# mbmc_single_board.net
KiCad netlist of a schematic drawn in EAGLE
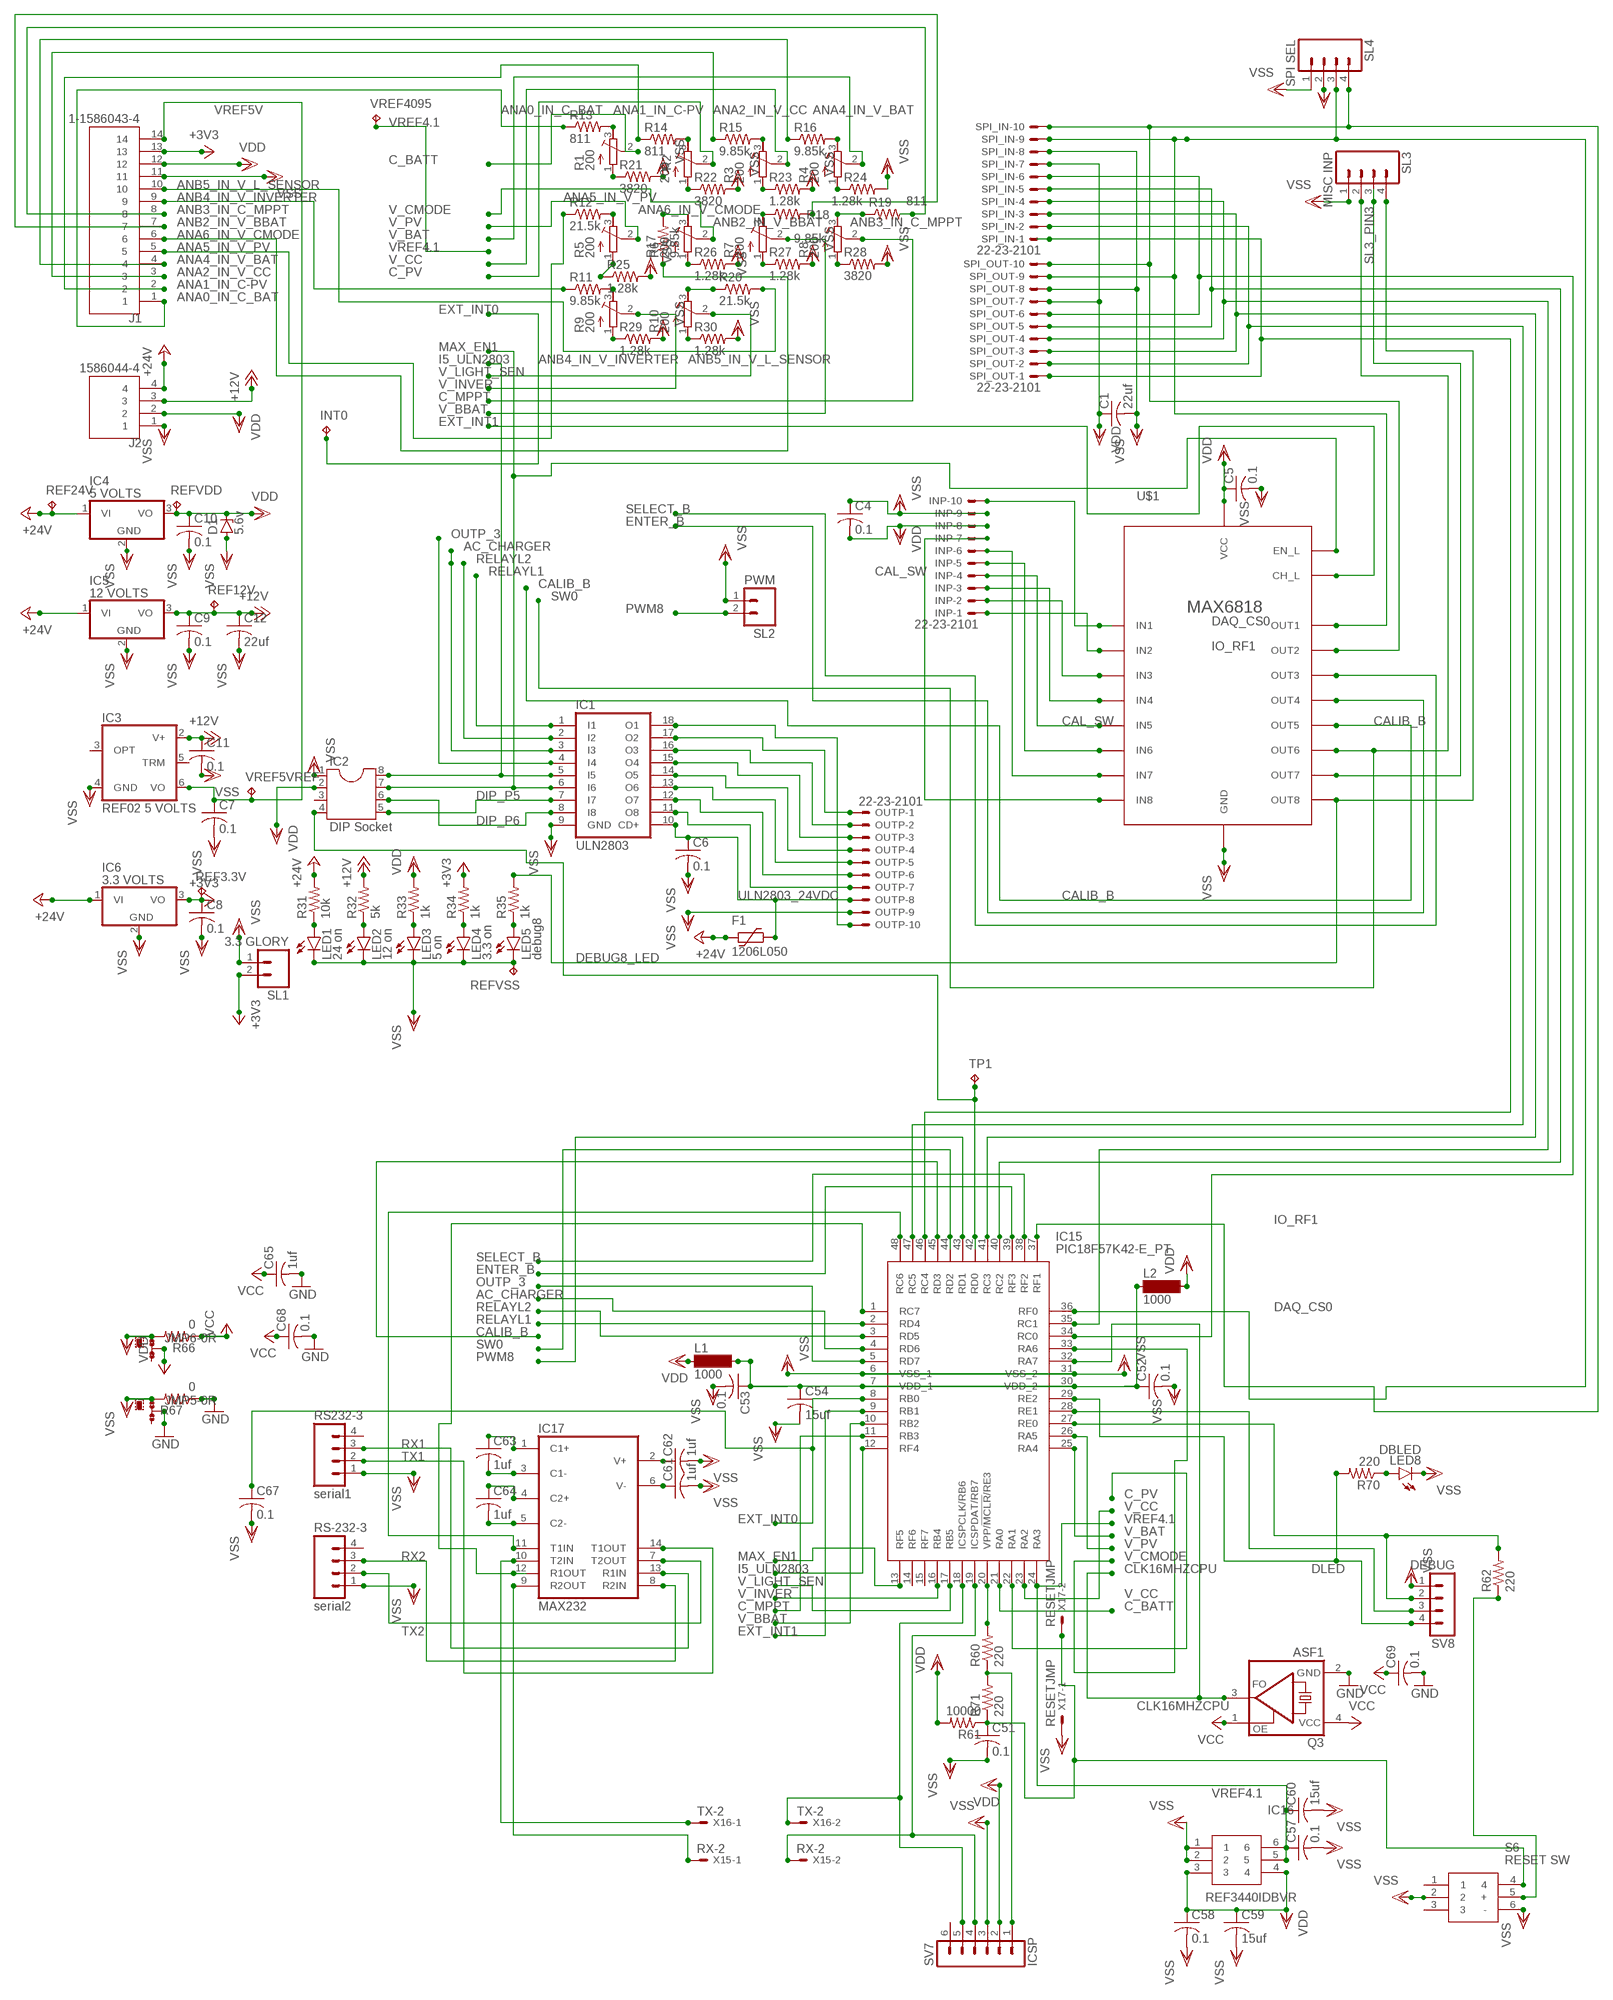
[diagram p0: schematic, sheet 1]

(export (version "E")
  (design (tool "Eeschema 10.0.6"))
  (components
    (comp (ref "C1")
      (value "22uf")
      (footprint "eagle-import:C0805")
      (libsource (lib "eagle-import") (part "C-USC0805"))
    )
    (comp (ref "C4")
      (value "0.1")
      (footprint "eagle-import:C0805")
      (libsource (lib "eagle-import") (part "C-USC0805"))
    )
    (comp (ref "C5")
      (value "0.1")
      (footprint "eagle-import:C0805")
      (libsource (lib "eagle-import") (part "C-USC0805"))
    )
    (comp (ref "C6")
      (value "0.1")
      (footprint "eagle-import:C0805")
      (libsource (lib "eagle-import") (part "C-USC0805"))
    )
    (comp (ref "C7")
      (value "0.1")
      (footprint "eagle-import:C0805")
      (libsource (lib "eagle-import") (part "C-USC0805"))
    )
    (comp (ref "C8")
      (value "0.1")
      (footprint "eagle-import:C0805")
      (libsource (lib "eagle-import") (part "C-USC0805"))
    )
    (comp (ref "C9")
      (value "0.1")
      (footprint "eagle-import:C0805")
      (libsource (lib "eagle-import") (part "C-USC0805"))
    )
    (comp (ref "C10")
      (value "0.1")
      (footprint "eagle-import:C0805")
      (libsource (lib "eagle-import") (part "C-USC0805"))
    )
    (comp (ref "C11")
      (value "0.1")
      (footprint "eagle-import:C0805")
      (libsource (lib "eagle-import") (part "C-USC0805"))
    )
    (comp (ref "C12")
      (value "22uf")
      (footprint "eagle-import:C0805")
      (libsource (lib "eagle-import") (part "C-USC0805"))
    )
    (comp (ref "C51")
      (value "0.1")
      (footprint "eagle-import:C1206")
      (libsource (lib "eagle-import") (part "C-USC1206"))
    )
    (comp (ref "C52")
      (value "0.1")
      (footprint "eagle-import:C1206")
      (libsource (lib "eagle-import") (part "C-USC1206"))
    )
    (comp (ref "C53")
      (value "0.1")
      (footprint "eagle-import:C1206")
      (libsource (lib "eagle-import") (part "C-USC1206"))
    )
    (comp (ref "C54")
      (value "15uf")
      (footprint "eagle-import:C1206")
      (libsource (lib "eagle-import") (part "C-USC1206"))
    )
    (comp (ref "C57")
      (value "0.1")
      (footprint "eagle-import:C1206")
      (libsource (lib "eagle-import") (part "C-USC1206"))
    )
    (comp (ref "C58")
      (value "0.1")
      (footprint "eagle-import:C1206")
      (libsource (lib "eagle-import") (part "C-USC1206"))
    )
    (comp (ref "C59")
      (value "15uf")
      (footprint "eagle-import:C1206")
      (libsource (lib "eagle-import") (part "C-USC1206"))
    )
    (comp (ref "C60")
      (value "15uf")
      (footprint "eagle-import:C1206")
      (libsource (lib "eagle-import") (part "C-USC1206"))
    )
    (comp (ref "C61")
      (value "1uf")
      (footprint "eagle-import:C0805")
      (libsource (lib "eagle-import") (part "C-USC0805"))
    )
    (comp (ref "C62")
      (value "1uf")
      (footprint "eagle-import:C0805")
      (libsource (lib "eagle-import") (part "C-USC0805"))
    )
    (comp (ref "C63")
      (value "1uf")
      (footprint "eagle-import:C0805")
      (libsource (lib "eagle-import") (part "C-USC0805"))
    )
    (comp (ref "C64")
      (value "1uf")
      (footprint "eagle-import:C0805")
      (libsource (lib "eagle-import") (part "C-USC0805"))
    )
    (comp (ref "C65")
      (value "1uf")
      (footprint "eagle-import:C0805")
      (libsource (lib "eagle-import") (part "C-USC0805"))
    )
    (comp (ref "C67")
      (value "0.1")
      (footprint "eagle-import:C1206")
      (libsource (lib "eagle-import") (part "C-USC1206"))
    )
    (comp (ref "C68")
      (value "0.1")
      (footprint "eagle-import:C1206")
      (libsource (lib "eagle-import") (part "C-USC1206"))
    )
    (comp (ref "C69")
      (value "0.1")
      (footprint "eagle-import:C1206")
      (libsource (lib "eagle-import") (part "C-USC1206"))
    )
    (comp (ref "D1")
      (value "5.6v")
      (footprint "eagle-import:ZDIO-2.5")
      (libsource (lib "eagle-import") (part "ZENER-DIODEZD-2.5"))
    )
    (comp (ref "F1")
      (value "1206L050")
      (footprint "eagle-import:1206L")
      (fields (field (name "MF") "Littelfuse"))
      (libsource (lib "eagle-import") (part "?1206L050"))
    )
    (comp (ref "IC1")
      (value "ULN2803")
      (footprint "eagle-import:DIL18")
      (libsource (lib "eagle-import") (part "ULN2803A"))
    )
    (comp (ref "IC2")
      (value "DIP Socket")
      (footprint "eagle-import:SOCKET-08")
      (libsource (lib "eagle-import") (part "DIL8S"))
    )
    (comp (ref "IC3")
      (value "REF02 5 VOLTS")
      (footprint "eagle-import:DIL08")
      (libsource (lib "eagle-import") (part "REF02Z"))
    )
    (comp (ref "IC4")
      (value "5 VOLTS")
      (footprint "eagle-import:TO220V")
      (libsource (lib "eagle-import") (part "78TV05"))
    )
    (comp (ref "IC5")
      (value "12 VOLTS")
      (footprint "eagle-import:TO220V")
      (libsource (lib "eagle-import") (part "78TV05"))
    )
    (comp (ref "IC6")
      (value "3.3 VOLTS")
      (footprint "eagle-import:TO220V")
      (libsource (lib "eagle-import") (part "78TV05"))
    )
    (comp (ref "IC15")
      (value "PIC18F57K42-E_PT")
      (footprint "eagle-import:QFP50P900X900X120-48N")
      (fields
        (field (name "MANUFACTURER_PART_NUMBER") "PIC18F57K42-E/PT")
        (field (name "MOUSER_PART_NUMBER") "579-PIC18F57K42-E/PT")
      )
      (libsource (lib "eagle-import") (part "PIC18F57K42-E_PT"))
    )
    (comp (ref "IC16")
      (value "REF3440IDBVR")
      (footprint "eagle-import:SOP95P280X145-6N")
      (libsource (lib "eagle-import") (part "REF3440IDBVR"))
    )
    (comp (ref "IC17")
      (value "MAX232")
      (footprint "eagle-import:DIL16")
      (fields (field (name "MF") "MAXIM") (field (name "MPN") "MAX232ACPE+"))
      (libsource (lib "eagle-import") (part "MAX232"))
    )
    (comp (ref "INP")
      (value "22-23-2101")
      (footprint "eagle-import:22-23-2101")
      (fields (field (name "MF") "MOLEX"))
      (libsource (lib "eagle-import") (part "22-23-2101"))
    )
    (comp (ref "INT0")
      (value "TPB1,27")
      (footprint "eagle-import:B1,27")
      (libsource (lib "eagle-import") (part "TPB1,27"))
    )
    (comp (ref "J1")
      (value "1-1586043-4")
      (footprint "eagle-import:TE_1-1586043-4")
      (fields (field (name "MANUFACTURER") "TE"))
      (libsource (lib "eagle-import") (part "1-1586043-4"))
    )
    (comp (ref "J2")
      (value "1586044-4")
      (footprint "eagle-import:TE_1586044-4")
      (fields (field (name "MANUFACTURER") "TE"))
      (libsource (lib "eagle-import") (part "1586044-4"))
    )
    (comp (ref "JMP5")
      (value "0R-JUMPA")
      (footprint "eagle-import:A0R-JMP")
      (libsource (lib "eagle-import") (part "0R-JUMPA"))
    )
    (comp (ref "JMP6")
      (value "0R-JUMPA")
      (footprint "eagle-import:A0R-JMP")
      (libsource (lib "eagle-import") (part "0R-JUMPA"))
    )
    (comp (ref "L1")
      (value "1000")
      (footprint "eagle-import:SM-1206")
      (libsource (lib "eagle-import") (part "SM-1206"))
    )
    (comp (ref "L2")
      (value "1000")
      (footprint "eagle-import:SM-1206")
      (libsource (lib "eagle-import") (part "SM-1206"))
    )
    (comp (ref "LED1")
      (value "24 on")
      (footprint "eagle-import:CHIPLED_1206")
      (libsource (lib "eagle-import") (part "LEDCHIPLED_1206"))
    )
    (comp (ref "LED2")
      (value "12 on")
      (footprint "eagle-import:CHIPLED_1206")
      (libsource (lib "eagle-import") (part "LEDCHIPLED_1206"))
    )
    (comp (ref "LED3")
      (value "5 on")
      (footprint "eagle-import:CHIPLED_1206")
      (libsource (lib "eagle-import") (part "LEDCHIPLED_1206"))
    )
    (comp (ref "LED4")
      (value "3.3 on")
      (footprint "eagle-import:CHIPLED_1206")
      (libsource (lib "eagle-import") (part "LEDCHIPLED_1206"))
    )
    (comp (ref "LED5")
      (value "debug8")
      (footprint "eagle-import:CHIPLED_1206")
      (libsource (lib "eagle-import") (part "LEDCHIPLED_1206"))
    )
    (comp (ref "LED8")
      (value "DBLED")
      (footprint "eagle-import:CHIPLED_1206")
      (libsource (lib "eagle-import") (part "LEDCHIPLED_1206"))
    )
    (comp (ref "OUTP")
      (value "22-23-2101")
      (footprint "eagle-import:22-23-2101")
      (fields (field (name "MF") "MOLEX"))
      (libsource (lib "eagle-import") (part "22-23-2101"))
    )
    (comp (ref "Q3")
      (value "ASF1")
      (footprint "eagle-import:ASF")
      (libsource (lib "eagle-import") (part "ASF1"))
    )
    (comp (ref "R1")
      (value "200")
      (footprint "eagle-import:RTRIM3339P")
      (libsource (lib "eagle-import") (part "R-TRIMM3339P"))
    )
    (comp (ref "R2")
      (value "200")
      (footprint "eagle-import:RTRIM3339P")
      (libsource (lib "eagle-import") (part "R-TRIMM3339P"))
    )
    (comp (ref "R3")
      (value "200")
      (footprint "eagle-import:RTRIM3339P")
      (libsource (lib "eagle-import") (part "R-TRIMM3339P"))
    )
    (comp (ref "R4")
      (value "200")
      (footprint "eagle-import:RTRIM3339P")
      (libsource (lib "eagle-import") (part "R-TRIMM3339P"))
    )
    (comp (ref "R5")
      (value "200")
      (footprint "eagle-import:RTRIM3339P")
      (libsource (lib "eagle-import") (part "R-TRIMM3339P"))
    )
    (comp (ref "R6")
      (value "200")
      (footprint "eagle-import:RTRIM3339P")
      (libsource (lib "eagle-import") (part "R-TRIMM3339P"))
    )
    (comp (ref "R7")
      (value "200")
      (footprint "eagle-import:RTRIM3339P")
      (libsource (lib "eagle-import") (part "R-TRIMM3339P"))
    )
    (comp (ref "R8")
      (value "200")
      (footprint "eagle-import:RTRIM3339P")
      (libsource (lib "eagle-import") (part "R-TRIMM3339P"))
    )
    (comp (ref "R9")
      (value "200")
      (footprint "eagle-import:RTRIM3339P")
      (libsource (lib "eagle-import") (part "R-TRIMM3339P"))
    )
    (comp (ref "R10")
      (value "200")
      (footprint "eagle-import:RTRIM3339P")
      (libsource (lib "eagle-import") (part "R-TRIMM3339P"))
    )
    (comp (ref "R11")
      (value "9.85k")
      (footprint "eagle-import:R0805")
      (libsource (lib "eagle-import") (part "R-US_R0805"))
    )
    (comp (ref "R12")
      (value "21.5k")
      (footprint "eagle-import:R0805")
      (libsource (lib "eagle-import") (part "R-US_R0805"))
    )
    (comp (ref "R13")
      (value "811")
      (footprint "eagle-import:R0805")
      (libsource (lib "eagle-import") (part "R-US_R0805"))
    )
    (comp (ref "R14")
      (value "811")
      (footprint "eagle-import:R0805")
      (libsource (lib "eagle-import") (part "R-US_R0805"))
    )
    (comp (ref "R15")
      (value "9.85k")
      (footprint "eagle-import:R0805")
      (libsource (lib "eagle-import") (part "R-US_R0805"))
    )
    (comp (ref "R16")
      (value "9.85k")
      (footprint "eagle-import:R0805")
      (libsource (lib "eagle-import") (part "R-US_R0805"))
    )
    (comp (ref "R17")
      (value "9.85k")
      (footprint "eagle-import:R0805")
      (libsource (lib "eagle-import") (part "R-US_R0805"))
    )
    (comp (ref "R18")
      (value "9.85k")
      (footprint "eagle-import:R0805")
      (libsource (lib "eagle-import") (part "R-US_R0805"))
    )
    (comp (ref "R19")
      (value "811")
      (footprint "eagle-import:R0805")
      (libsource (lib "eagle-import") (part "R-US_R0805"))
    )
    (comp (ref "R20")
      (value "21.5k")
      (footprint "eagle-import:R0805")
      (libsource (lib "eagle-import") (part "R-US_R0805"))
    )
    (comp (ref "R21")
      (value "3820")
      (footprint "eagle-import:R0805")
      (libsource (lib "eagle-import") (part "R-US_R0805"))
    )
    (comp (ref "R22")
      (value "3820")
      (footprint "eagle-import:R0805")
      (libsource (lib "eagle-import") (part "R-US_R0805"))
    )
    (comp (ref "R23")
      (value "1.28k")
      (footprint "eagle-import:R0805")
      (libsource (lib "eagle-import") (part "R-US_R0805"))
    )
    (comp (ref "R24")
      (value "1.28k")
      (footprint "eagle-import:R0805")
      (libsource (lib "eagle-import") (part "R-US_R0805"))
    )
    (comp (ref "R25")
      (value "1.28k")
      (footprint "eagle-import:R0805")
      (libsource (lib "eagle-import") (part "R-US_R0805"))
    )
    (comp (ref "R26")
      (value "1.28k")
      (footprint "eagle-import:R0805")
      (libsource (lib "eagle-import") (part "R-US_R0805"))
    )
    (comp (ref "R27")
      (value "1.28k")
      (footprint "eagle-import:R0805")
      (libsource (lib "eagle-import") (part "R-US_R0805"))
    )
    (comp (ref "R28")
      (value "3820")
      (footprint "eagle-import:R0805")
      (libsource (lib "eagle-import") (part "R-US_R0805"))
    )
    (comp (ref "R29")
      (value "1.28k")
      (footprint "eagle-import:R0805")
      (libsource (lib "eagle-import") (part "R-US_R0805"))
    )
    (comp (ref "R30")
      (value "1.28k")
      (footprint "eagle-import:R0805")
      (libsource (lib "eagle-import") (part "R-US_R0805"))
    )
    (comp (ref "R31")
      (value "10k")
      (footprint "eagle-import:R0805")
      (libsource (lib "eagle-import") (part "R-US_R0805"))
    )
    (comp (ref "R32")
      (value "5k")
      (footprint "eagle-import:R0805")
      (libsource (lib "eagle-import") (part "R-US_R0805"))
    )
    (comp (ref "R33")
      (value "1k")
      (footprint "eagle-import:R0805")
      (libsource (lib "eagle-import") (part "R-US_R0805"))
    )
    (comp (ref "R34")
      (value "1k")
      (footprint "eagle-import:R0805")
      (libsource (lib "eagle-import") (part "R-US_R0805"))
    )
    (comp (ref "R35")
      (value "1k")
      (footprint "eagle-import:R0805")
      (libsource (lib "eagle-import") (part "R-US_R0805"))
    )
    (comp (ref "R60")
      (value "220")
      (footprint "eagle-import:R1206")
      (libsource (lib "eagle-import") (part "R-US_R1206"))
    )
    (comp (ref "R61")
      (value "10000")
      (footprint "eagle-import:R1206")
      (libsource (lib "eagle-import") (part "R-US_R1206"))
    )
    (comp (ref "R62")
      (value "220")
      (footprint "eagle-import:R1206")
      (libsource (lib "eagle-import") (part "R-US_R1206"))
    )
    (comp (ref "R66")
      (value "0")
      (footprint "eagle-import:R1206")
      (libsource (lib "eagle-import") (part "R-US_R1206"))
    )
    (comp (ref "R67")
      (value "0")
      (footprint "eagle-import:R1206")
      (libsource (lib "eagle-import") (part "R-US_R1206"))
    )
    (comp (ref "R70")
      (value "220")
      (footprint "eagle-import:R1206")
      (libsource (lib "eagle-import") (part "R-US_R1206"))
    )
    (comp (ref "R71")
      (value "220")
      (footprint "eagle-import:R1206")
      (libsource (lib "eagle-import") (part "R-US_R1206"))
    )
    (comp (ref "REF3.3V")
      (value "TPB1,27")
      (footprint "eagle-import:B1,27")
      (libsource (lib "eagle-import") (part "TPB1,27"))
    )
    (comp (ref "REF12V")
      (value "TPB1,27")
      (footprint "eagle-import:B1,27")
      (libsource (lib "eagle-import") (part "TPB1,27"))
    )
    (comp (ref "REF24V")
      (value "TPB1,27")
      (footprint "eagle-import:B1,27")
      (libsource (lib "eagle-import") (part "TPB1,27"))
    )
    (comp (ref "REFVDD")
      (value "TPB1,27")
      (footprint "eagle-import:B1,27")
      (libsource (lib "eagle-import") (part "TPB1,27"))
    )
    (comp (ref "REFVSS")
      (value "TPB1,27")
      (footprint "eagle-import:B1,27")
      (libsource (lib "eagle-import") (part "TPB1,27"))
    )
    (comp (ref "RS-232-3")
      (value "serial2")
      (footprint "eagle-import:04P")
      (libsource (lib "eagle-import") (part "M04"))
    )
    (comp (ref "RS232-3")
      (value "serial1")
      (footprint "eagle-import:04P")
      (libsource (lib "eagle-import") (part "M04"))
    )
    (comp (ref "S6")
      (value "RESET SW")
      (footprint "eagle-import:B3W-9_1-LED")
      (fields
        (field (name "MANUFACTURER_PART_NUMBER") "B3W-9000-Y1N")
        (field (name "MOUSER_PART_NUMBER") "653-B3W-9000-Y1N")
        (field (name "RS_PART_NUMBER") "0492777P")
      )
      (libsource (lib "eagle-import") (part "B3W-9000-Y1N"))
    )
    (comp (ref "SL1")
      (value "3.3 GLORY")
      (footprint "eagle-import:02P")
      (libsource (lib "eagle-import") (part "M02"))
    )
    (comp (ref "SL2")
      (value "PWM")
      (footprint "eagle-import:02P")
      (libsource (lib "eagle-import") (part "M02"))
    )
    (comp (ref "SL3")
      (value "MISC INP")
      (footprint "eagle-import:04P")
      (libsource (lib "eagle-import") (part "M04"))
    )
    (comp (ref "SL4")
      (value "SPI SEL")
      (footprint "eagle-import:04P")
      (libsource (lib "eagle-import") (part "M04"))
    )
    (comp (ref "SPI_IN")
      (value "22-23-2101")
      (footprint "eagle-import:22-23-2101")
      (fields (field (name "MF") "MOLEX"))
      (libsource (lib "eagle-import") (part "22-23-2101"))
    )
    (comp (ref "SPI_OUT")
      (value "22-23-2101")
      (footprint "eagle-import:22-23-2101")
      (fields (field (name "MF") "MOLEX"))
      (libsource (lib "eagle-import") (part "22-23-2101"))
    )
    (comp (ref "SV7")
      (value "ICSP")
      (footprint "eagle-import:MA06-1")
      (libsource (lib "eagle-import") (part "MA06-1"))
    )
    (comp (ref "SV8")
      (value "DEBUG")
      (footprint "eagle-import:MA04-1")
      (libsource (lib "eagle-import") (part "MA04-1"))
    )
    (comp (ref "TP1")
      (value "TPB1,27")
      (footprint "eagle-import:B1,27")
      (libsource (lib "eagle-import") (part "TPB1,27"))
    )
    (comp (ref "U$1")
      (value "MAX6818")
      (footprint "eagle-import:SSOP20")
      (fields (field (name "MF") "Maxim Integrated"))
      (libsource (lib "eagle-import") (part "MAX6818"))
    )
    (comp (ref "VREF5VREF")
      (value "TPB1,27")
      (footprint "eagle-import:B1,27")
      (libsource (lib "eagle-import") (part "TPB1,27"))
    )
    (comp (ref "VREF4095")
      (value "TPB1,27")
      (footprint "eagle-import:B1,27")
      (libsource (lib "eagle-import") (part "TPB1,27"))
    )
    (comp (ref "X15")
      (value "RX-2")
      (footprint "eagle-import:332-02")
      (libsource (lib "eagle-import") (part "332-02"))
    )
    (comp (ref "X16")
      (value "TX-2")
      (footprint "eagle-import:332-02")
      (libsource (lib "eagle-import") (part "332-02"))
    )
    (comp (ref "X17")
      (value "RESETJMP")
      (footprint "eagle-import:332-02")
      (libsource (lib "eagle-import") (part "332-02"))
    )
  )
  (nets
    (net (code "1") (name "+3V3") (class "Default")
      (node (ref "C8") (pin "1") (pinfunction "1_1") (pintype "passive"))
      (node (ref "IC6") (pin "3") (pinfunction "VO_3") (pintype "passive"))
      (node (ref "J1") (pin "13") (pinfunction "13_13") (pintype "passive"))
      (node (ref "R34") (pin "2") (pinfunction "2_2") (pintype "passive"))
      (node (ref "REF3.3V") (pin "TP") (pinfunction "TP_TP") (pintype "input"))
      (node (ref "SL1") (pin "2") (pinfunction "2_2") (pintype "passive"))
    )
    (net (code "2") (name "+12V") (class "Default")
      (node (ref "C11") (pin "1") (pinfunction "1_1") (pintype "passive"))
      (node (ref "C12") (pin "1") (pinfunction "1_1") (pintype "passive"))
      (node (ref "C9") (pin "1") (pinfunction "1_1") (pintype "passive"))
      (node (ref "IC3") (pin "2") (pinfunction "V+_2") (pintype "power_in"))
      (node (ref "IC5") (pin "3") (pinfunction "VO_3") (pintype "passive"))
      (node (ref "J2") (pin "3") (pinfunction "3_3") (pintype "passive"))
      (node (ref "R32") (pin "2") (pinfunction "2_2") (pintype "passive"))
      (node (ref "REF12V") (pin "TP") (pinfunction "TP_TP") (pintype "input"))
    )
    (net (code "3") (name "+24V") (class "Default")
      (node (ref "F1") (pin "2") (pinfunction "2_2") (pintype "passive"))
      (node (ref "IC4") (pin "1") (pinfunction "VI_1") (pintype "input"))
      (node (ref "IC5") (pin "1") (pinfunction "VI_1") (pintype "input"))
      (node (ref "IC6") (pin "1") (pinfunction "VI_1") (pintype "input"))
      (node (ref "J2") (pin "4") (pinfunction "4_4") (pintype "passive"))
      (node (ref "R31") (pin "2") (pinfunction "2_2") (pintype "passive"))
      (node (ref "REF24V") (pin "TP") (pinfunction "TP_TP") (pintype "input"))
    )
    (net (code "4") (name "/AC_CHARGER") (class "Default")
      (node (ref "IC1") (pin "3") (pinfunction "I3_3") (pintype "input"))
      (node (ref "IC15") (pin "4") (pinfunction "RD6_4") (pintype "bidirectional"))
    )
    (net (code "5") (name "/ANA0_IN_C_BAT") (class "Default")
      (node (ref "J1") (pin "1") (pinfunction "1_1") (pintype "passive"))
      (node (ref "R13") (pin "1") (pinfunction "1_1") (pintype "passive"))
    )
    (net (code "6") (name "/ANA1_IN_C-PV") (class "Default")
      (node (ref "J1") (pin "2") (pinfunction "2_2") (pintype "passive"))
      (node (ref "R14") (pin "1") (pinfunction "1_1") (pintype "passive"))
    )
    (net (code "7") (name "/ANA2_IN_V_CC") (class "Default")
      (node (ref "J1") (pin "3") (pinfunction "3_3") (pintype "passive"))
      (node (ref "R15") (pin "1") (pinfunction "1_1") (pintype "passive"))
    )
    (net (code "8") (name "/ANA4_IN_V_BAT") (class "Default")
      (node (ref "J1") (pin "4") (pinfunction "4_4") (pintype "passive"))
      (node (ref "R16") (pin "1") (pinfunction "1_1") (pintype "passive"))
    )
    (net (code "9") (name "/ANA5_IN_V_PV") (class "Default")
      (node (ref "J1") (pin "5") (pinfunction "5_5") (pintype "passive"))
      (node (ref "R12") (pin "1") (pinfunction "1_1") (pintype "passive"))
    )
    (net (code "10") (name "/ANA6_IN_V_CMODE") (class "Default")
      (node (ref "J1") (pin "6") (pinfunction "6_6") (pintype "passive"))
      (node (ref "R17") (pin "1") (pinfunction "1_1") (pintype "passive"))
    )
    (net (code "11") (name "/ANB2_IN_V_BBAT") (class "Default")
      (node (ref "J1") (pin "7") (pinfunction "7_7") (pintype "passive"))
      (node (ref "R18") (pin "2") (pinfunction "2_2") (pintype "passive"))
    )
    (net (code "12") (name "/ANB3_IN_C_MPPT") (class "Default")
      (node (ref "J1") (pin "8") (pinfunction "8_8") (pintype "passive"))
      (node (ref "R19") (pin "2") (pinfunction "2_2") (pintype "passive"))
    )
    (net (code "13") (name "/ANB4_IN_V_INVERTER") (class "Default")
      (node (ref "J1") (pin "9") (pinfunction "9_9") (pintype "passive"))
      (node (ref "R11") (pin "1") (pinfunction "1_1") (pintype "passive"))
    )
    (net (code "14") (name "/ANB5_IN_V_L_SENSOR") (class "Default")
      (node (ref "J1") (pin "10") (pinfunction "10_10") (pintype "passive"))
      (node (ref "R20") (pin "2") (pinfunction "2_2") (pintype "passive"))
    )
    (net (code "15") (name "/CALIB_B") (class "Default")
      (node (ref "IC15") (pin "45") (pinfunction "RD3_45") (pintype "bidirectional"))
      (node (ref "U$1") (pin "OUT5") (pinfunction "OUT5_OUT5") (pintype "bidirectional"))
    )
    (net (code "16") (name "/CAL_SW") (class "Default")
      (node (ref "INP") (pin "4") (pinfunction "S_4") (pintype "passive"))
      (node (ref "U$1") (pin "IN5") (pinfunction "IN5_IN5") (pintype "bidirectional"))
    )
    (net (code "17") (name "/CLK16MHZCPU") (class "Default")
      (node (ref "IC15") (pin "32") (pinfunction "RA7_32") (pintype "bidirectional"))
      (node (ref "Q3") (pin "3") (pinfunction "FO_3") (pintype "output"))
    )
    (net (code "18") (name "/C_BATT") (class "Default")
      (node (ref "IC15") (pin "21") (pinfunction "RA0_21") (pintype "bidirectional"))
      (node (ref "R1") (pin "2") (pinfunction "S_2") (pintype "passive"))
    )
    (net (code "19") (name "/C_MPPT") (class "Default")
      (node (ref "IC15") (pin "11") (pinfunction "RB3_11") (pintype "bidirectional"))
      (node (ref "R8") (pin "2") (pinfunction "S_2") (pintype "passive"))
    )
    (net (code "20") (name "/C_PV") (class "Default")
      (node (ref "IC15") (pin "22") (pinfunction "RA1_22") (pintype "bidirectional"))
      (node (ref "R2") (pin "2") (pinfunction "S_2") (pintype "passive"))
    )
    (net (code "21") (name "/DAQ_CS0") (class "Default")
      (node (ref "IC15") (pin "36") (pinfunction "RF0_36") (pintype "bidirectional"))
      (node (ref "SL4") (pin "3") (pinfunction "3_3") (pintype "passive"))
      (node (ref "SPI_IN") (pin "9") (pinfunction "S_9") (pintype "passive"))
      (node (ref "SPI_OUT") (pin "9") (pinfunction "S_9") (pintype "passive"))
      (node (ref "U$1") (pin "OUT1") (pinfunction "OUT1_OUT1") (pintype "bidirectional"))
    )
    (net (code "22") (name "/DEBUG8_LED") (class "Default")
      (node (ref "R35") (pin "2") (pinfunction "2_2") (pintype "passive"))
      (node (ref "SL3") (pin "4") (pinfunction "4_4") (pintype "passive"))
      (node (ref "U$1") (pin "OUT8") (pinfunction "OUT8_OUT8") (pintype "bidirectional"))
    )
    (net (code "23") (name "/DIP_P5") (class "Default")
      (node (ref "IC1") (pin "7") (pinfunction "I7_7") (pintype "input"))
      (node (ref "IC2") (pin "5") (pinfunction "5_5") (pintype "passive"))
    )
    (net (code "24") (name "/DIP_P6") (class "Default")
      (node (ref "IC1") (pin "8") (pinfunction "I8_8") (pintype "input"))
      (node (ref "IC2") (pin "6") (pinfunction "6_6") (pintype "passive"))
    )
    (net (code "25") (name "/DLED") (class "Default")
      (node (ref "IC15") (pin "29") (pinfunction "RE2_29") (pintype "bidirectional"))
      (node (ref "R70") (pin "2") (pinfunction "2_2") (pintype "passive"))
      (node (ref "SV8") (pin "4") (pinfunction "4_4") (pintype "passive"))
    )
    (net (code "26") (name "/ENTER_B") (class "Default")
      (node (ref "IC15") (pin "39") (pinfunction "RF3_39") (pintype "bidirectional"))
      (node (ref "U$1") (pin "OUT4") (pinfunction "OUT4_OUT4") (pintype "bidirectional"))
    )
    (net (code "27") (name "/EXT_INT0") (class "Default")
      (node (ref "C67") (pin "1") (pinfunction "1_1") (pintype "passive"))
      (node (ref "IC15") (pin "8") (pinfunction "RB0_8") (pintype "bidirectional"))
      (node (ref "INT0") (pin "TP") (pinfunction "TP_TP") (pintype "input"))
    )
    (net (code "28") (name "/EXT_INT1") (class "Default")
      (node (ref "IC15") (pin "9") (pinfunction "RB1_9") (pintype "bidirectional"))
      (node (ref "U$1") (pin "CH_L") (pinfunction "CH_L_CH_L") (pintype "bidirectional"))
    )
    (net (code "29") (name "/I5_ULN2803") (class "Default")
      (node (ref "IC1") (pin "5") (pinfunction "I5_5") (pintype "input"))
      (node (ref "IC15") (pin "12") (pinfunction "RF4_12") (pintype "bidirectional"))
      (node (ref "IC2") (pin "8") (pinfunction "8_8") (pintype "passive"))
    )
    (net (code "30") (name "/IO_RF1") (class "Default")
      (node (ref "IC15") (pin "37") (pinfunction "RF1_37") (pintype "bidirectional"))
      (node (ref "SL4") (pin "4") (pinfunction "4_4") (pintype "passive"))
      (node (ref "SPI_IN") (pin "10") (pinfunction "S_10") (pintype "passive"))
      (node (ref "SPI_OUT") (pin "10") (pinfunction "S_10") (pintype "passive"))
      (node (ref "U$1") (pin "OUT2") (pinfunction "OUT2_OUT2") (pintype "bidirectional"))
    )
    (net (code "31") (name "/MAX_EN1") (class "Default")
      (node (ref "IC1") (pin "6") (pinfunction "I6_6") (pintype "input"))
      (node (ref "IC15") (pin "13") (pinfunction "RF5_13") (pintype "bidirectional"))
      (node (ref "IC2") (pin "7") (pinfunction "7_7") (pintype "passive"))
      (node (ref "U$1") (pin "EN_L") (pinfunction "EN_L_EN_L") (pintype "bidirectional"))
    )
    (net (code "32") (name "/OUTP_3") (class "Default")
      (node (ref "IC1") (pin "4") (pinfunction "I4_4") (pintype "input"))
      (node (ref "IC15") (pin "5") (pinfunction "RD7_5") (pintype "bidirectional"))
    )
    (net (code "33") (name "/PWM8") (class "Default")
      (node (ref "IC15") (pin "43") (pinfunction "RD1_43") (pintype "bidirectional"))
      (node (ref "SL2") (pin "2") (pinfunction "2_2") (pintype "passive"))
    )
    (net (code "34") (name "/RELAYL1") (class "Default")
      (node (ref "IC1") (pin "1") (pinfunction "I1_1") (pintype "input"))
      (node (ref "IC15") (pin "2") (pinfunction "RD4_2") (pintype "bidirectional"))
    )
    (net (code "35") (name "/RELAYL2") (class "Default")
      (node (ref "IC1") (pin "2") (pinfunction "I2_2") (pintype "input"))
      (node (ref "IC15") (pin "3") (pinfunction "RD5_3") (pintype "bidirectional"))
    )
    (net (code "36") (name "/RX1") (class "Default")
      (node (ref "IC17") (pin "13") (pinfunction "R1IN_13") (pintype "input"))
      (node (ref "RS232-3") (pin "3") (pinfunction "3_3") (pintype "passive"))
    )
    (net (code "37") (name "/RX2") (class "Default")
      (node (ref "IC17") (pin "8") (pinfunction "R2IN_8") (pintype "input"))
      (node (ref "RS-232-3") (pin "3") (pinfunction "3_3") (pintype "passive"))
    )
    (net (code "38") (name "/SELECT_B") (class "Default")
      (node (ref "IC15") (pin "38") (pinfunction "RF2_38") (pintype "bidirectional"))
      (node (ref "U$1") (pin "OUT3") (pinfunction "OUT3_OUT3") (pintype "bidirectional"))
    )
    (net (code "39") (name "/SL3_PIN3") (class "Default")
      (node (ref "SL3") (pin "3") (pinfunction "3_3") (pintype "passive"))
      (node (ref "U$1") (pin "OUT7") (pinfunction "OUT7_OUT7") (pintype "bidirectional"))
    )
    (net (code "40") (name "/SW0") (class "Default")
      (node (ref "IC15") (pin "44") (pinfunction "RD2_44") (pintype "bidirectional"))
      (node (ref "SL3") (pin "2") (pinfunction "2_2") (pintype "passive"))
      (node (ref "U$1") (pin "OUT6") (pinfunction "OUT6_OUT6") (pintype "bidirectional"))
    )
    (net (code "41") (name "/TX1") (class "Default")
      (node (ref "IC17") (pin "14") (pinfunction "T1OUT_14") (pintype "output"))
      (node (ref "RS232-3") (pin "2") (pinfunction "2_2") (pintype "passive"))
    )
    (net (code "42") (name "/TX2") (class "Default")
      (node (ref "IC17") (pin "7") (pinfunction "T2OUT_7") (pintype "output"))
      (node (ref "RS-232-3") (pin "2") (pinfunction "2_2") (pintype "passive"))
    )
    (net (code "43") (name "/ULN2803_24VDC") (class "Default")
      (node (ref "C6") (pin "1") (pinfunction "1_1") (pintype "passive"))
      (node (ref "F1") (pin "1") (pinfunction "1_1") (pintype "passive"))
      (node (ref "IC1") (pin "10") (pinfunction "CD+_10") (pintype "passive"))
      (node (ref "OUTP") (pin "8") (pinfunction "S_8") (pintype "passive"))
    )
    (net (code "44") (name "/VREF4.1") (class "Default")
      (node (ref "C57") (pin "1") (pinfunction "1_1") (pintype "passive"))
      (node (ref "C60") (pin "1") (pinfunction "1_1") (pintype "passive"))
      (node (ref "IC15") (pin "24") (pinfunction "RA3_24") (pintype "bidirectional"))
      (node (ref "IC16") (pin "5") (pinfunction "5_5") (pintype "bidirectional"))
      (node (ref "IC16") (pin "6") (pinfunction "6_6") (pintype "bidirectional"))
      (node (ref "VREF4095") (pin "TP") (pinfunction "TP_TP") (pintype "input"))
    )
    (net (code "45") (name "/VREF5V") (class "Default")
      (node (ref "C7") (pin "1") (pinfunction "1_1") (pintype "passive"))
      (node (ref "IC3") (pin "6") (pinfunction "VO_6") (pintype "output"))
      (node (ref "J1") (pin "14") (pinfunction "14_14") (pintype "passive"))
      (node (ref "VREF5VREF") (pin "TP") (pinfunction "TP_TP") (pintype "input"))
    )
    (net (code "46") (name "/V_BAT") (class "Default")
      (node (ref "IC15") (pin "25") (pinfunction "RA4_25") (pintype "bidirectional"))
      (node (ref "R4") (pin "2") (pinfunction "S_2") (pintype "passive"))
    )
    (net (code "47") (name "/V_BBAT") (class "Default")
      (node (ref "IC15") (pin "10") (pinfunction "RB2_10") (pintype "bidirectional"))
      (node (ref "R7") (pin "2") (pinfunction "S_2") (pintype "passive"))
    )
    (net (code "48") (name "/V_CC") (class "Default")
      (node (ref "IC15") (pin "23") (pinfunction "RA2_23") (pintype "bidirectional"))
      (node (ref "R3") (pin "2") (pinfunction "S_2") (pintype "passive"))
    )
    (net (code "49") (name "/V_CMODE") (class "Default")
      (node (ref "IC15") (pin "33") (pinfunction "RA6_33") (pintype "bidirectional"))
      (node (ref "R6") (pin "2") (pinfunction "S_2") (pintype "passive"))
    )
    (net (code "50") (name "/V_INVER") (class "Default")
      (node (ref "IC15") (pin "16") (pinfunction "RB4_16") (pintype "bidirectional"))
      (node (ref "R9") (pin "2") (pinfunction "S_2") (pintype "passive"))
    )
    (net (code "51") (name "/V_LIGHT_SEN") (class "Default")
      (node (ref "IC15") (pin "17") (pinfunction "RB5_17") (pintype "bidirectional"))
      (node (ref "R10") (pin "2") (pinfunction "S_2") (pintype "passive"))
    )
    (net (code "52") (name "/V_PV") (class "Default")
      (node (ref "IC15") (pin "26") (pinfunction "RA5_26") (pintype "bidirectional"))
      (node (ref "R5") (pin "2") (pinfunction "S_2") (pintype "passive"))
    )
    (net (code "53") (name "GND") (class "Default")
      (node (ref "C65") (pin "2") (pinfunction "2_2") (pintype "passive"))
      (node (ref "C68") (pin "2") (pinfunction "2_2") (pintype "passive"))
      (node (ref "C69") (pin "2") (pinfunction "2_2") (pintype "passive"))
      (node (ref "JMP5") (pin "2") (pinfunction "2_2") (pintype "passive"))
      (node (ref "Q3") (pin "2") (pinfunction "GND_2") (pintype "power_in"))
      (node (ref "R67") (pin "1") (pinfunction "1_1") (pintype "passive"))
    )
    (net (code "54") (name "Net-(IC1-O1)") (class "Default")
      (node (ref "IC1") (pin "18") (pinfunction "O1_18") (pintype "open_collector"))
      (node (ref "OUTP") (pin "10") (pinfunction "S_10") (pintype "passive"))
    )
    (net (code "55") (name "Net-(IC1-O2)") (class "Default")
      (node (ref "IC1") (pin "17") (pinfunction "O2_17") (pintype "open_collector"))
      (node (ref "OUTP") (pin "1") (pinfunction "S_1") (pintype "passive"))
    )
    (net (code "56") (name "Net-(IC1-O3)") (class "Default")
      (node (ref "IC1") (pin "16") (pinfunction "O3_16") (pintype "open_collector"))
      (node (ref "OUTP") (pin "2") (pinfunction "S_2") (pintype "passive"))
    )
    (net (code "57") (name "Net-(IC1-O4)") (class "Default")
      (node (ref "IC1") (pin "15") (pinfunction "O4_15") (pintype "open_collector"))
      (node (ref "OUTP") (pin "3") (pinfunction "S_3") (pintype "passive"))
    )
    (net (code "58") (name "Net-(IC1-O5)") (class "Default")
      (node (ref "IC1") (pin "14") (pinfunction "O5_14") (pintype "open_collector"))
      (node (ref "OUTP") (pin "4") (pinfunction "S_4") (pintype "passive"))
    )
    (net (code "59") (name "Net-(IC1-O6)") (class "Default")
      (node (ref "IC1") (pin "13") (pinfunction "O6_13") (pintype "open_collector"))
      (node (ref "OUTP") (pin "5") (pinfunction "S_5") (pintype "passive"))
    )
    (net (code "60") (name "Net-(IC1-O7)") (class "Default")
      (node (ref "IC1") (pin "12") (pinfunction "O7_12") (pintype "open_collector"))
      (node (ref "OUTP") (pin "6") (pinfunction "S_6") (pintype "passive"))
    )
    (net (code "61") (name "Net-(IC1-O8)") (class "Default")
      (node (ref "IC1") (pin "11") (pinfunction "O8_11") (pintype "open_collector"))
      (node (ref "OUTP") (pin "7") (pinfunction "S_7") (pintype "passive"))
    )
    (net (code "62") (name "Net-(IC15-ICSPCLK{slash}RB6)") (class "Default")
      (node (ref "IC15") (pin "18") (pinfunction "ICSPCLK/RB6_18") (pintype "bidirectional"))
      (node (ref "SV7") (pin "5") (pinfunction "5_5") (pintype "passive"))
      (node (ref "X16") (pin "2") (pinfunction "S_2") (pintype "passive"))
    )
    (net (code "63") (name "Net-(IC15-ICSPDAT{slash}RB7)") (class "Default")
      (node (ref "IC15") (pin "19") (pinfunction "ICSPDAT/RB7_19") (pintype "bidirectional"))
      (node (ref "SV7") (pin "4") (pinfunction "4_4") (pintype "passive"))
      (node (ref "X15") (pin "2") (pinfunction "S_2") (pintype "passive"))
    )
    (net (code "64") (name "Net-(IC15-RC0)") (class "Default")
      (node (ref "IC15") (pin "34") (pinfunction "RC0_34") (pintype "bidirectional"))
      (node (ref "SPI_IN") (pin "6") (pinfunction "S_6") (pintype "passive"))
      (node (ref "SPI_OUT") (pin "6") (pinfunction "S_6") (pintype "passive"))
    )
    (net (code "65") (name "Net-(IC15-RC1)") (class "Default")
      (node (ref "IC15") (pin "35") (pinfunction "RC1_35") (pintype "bidirectional"))
      (node (ref "SPI_IN") (pin "4") (pinfunction "S_4") (pintype "passive"))
      (node (ref "SPI_OUT") (pin "4") (pinfunction "S_4") (pintype "passive"))
    )
    (net (code "66") (name "Net-(IC15-RC2)") (class "Default")
      (node (ref "IC15") (pin "40") (pinfunction "RC2_40") (pintype "bidirectional"))
      (node (ref "SPI_IN") (pin "5") (pinfunction "S_5") (pintype "passive"))
      (node (ref "SPI_OUT") (pin "5") (pinfunction "S_5") (pintype "passive"))
    )
    (net (code "67") (name "Net-(IC15-RC3)") (class "Default")
      (node (ref "IC15") (pin "41") (pinfunction "RC3_41") (pintype "bidirectional"))
      (node (ref "SPI_IN") (pin "3") (pinfunction "S_3") (pintype "passive"))
      (node (ref "SPI_OUT") (pin "3") (pinfunction "S_3") (pintype "passive"))
    )
    (net (code "68") (name "Net-(IC15-RC4)") (class "Default")
      (node (ref "IC15") (pin "46") (pinfunction "RC4_46") (pintype "bidirectional"))
      (node (ref "SPI_IN") (pin "1") (pinfunction "S_1") (pintype "passive"))
      (node (ref "SPI_OUT") (pin "1") (pinfunction "S_1") (pintype "passive"))
    )
    (net (code "69") (name "Net-(IC15-RC5)") (class "Default")
      (node (ref "IC15") (pin "47") (pinfunction "RC5_47") (pintype "bidirectional"))
      (node (ref "SPI_IN") (pin "2") (pinfunction "S_2") (pintype "passive"))
      (node (ref "SPI_OUT") (pin "2") (pinfunction "S_2") (pintype "passive"))
    )
    (net (code "70") (name "Net-(IC15-RC6)") (class "Default")
      (node (ref "IC15") (pin "48") (pinfunction "RC6_48") (pintype "bidirectional"))
      (node (ref "IC17") (pin "11") (pinfunction "T1IN_11") (pintype "input"))
    )
    (net (code "71") (name "Net-(IC15-RC7)") (class "Default")
      (node (ref "IC15") (pin "1") (pinfunction "RC7_1") (pintype "bidirectional"))
      (node (ref "IC17") (pin "12") (pinfunction "R1OUT_12") (pintype "output"))
    )
    (net (code "72") (name "Net-(IC15-RD0)") (class "Default")
      (node (ref "IC15") (pin "42") (pinfunction "RD0_42") (pintype "bidirectional"))
      (node (ref "IC2") (pin "4") (pinfunction "4_4") (pintype "passive"))
      (node (ref "TP1") (pin "TP") (pinfunction "TP_TP") (pintype "input"))
    )
    (net (code "73") (name "Net-(IC15-RE0)") (class "Default")
      (node (ref "IC15") (pin "27") (pinfunction "RE0_27") (pintype "bidirectional"))
      (node (ref "R62") (pin "2") (pinfunction "2_2") (pintype "passive"))
      (node (ref "SV8") (pin "2") (pinfunction "2_2") (pintype "passive"))
    )
    (net (code "74") (name "Net-(IC15-RE1)") (class "Default")
      (node (ref "IC15") (pin "28") (pinfunction "RE1_28") (pintype "bidirectional"))
      (node (ref "SV8") (pin "3") (pinfunction "3_3") (pintype "passive"))
    )
    (net (code "75") (name "Net-(IC15-VDD_1)") (class "Default")
      (node (ref "C52") (pin "1") (pinfunction "1_1") (pintype "passive"))
      (node (ref "C53") (pin "1") (pinfunction "1_1") (pintype "passive"))
      (node (ref "C54") (pin "1") (pinfunction "1_1") (pintype "passive"))
      (node (ref "IC15") (pin "30") (pinfunction "VDD_2_30") (pintype "bidirectional"))
      (node (ref "IC15") (pin "7") (pinfunction "VDD_1_7") (pintype "bidirectional"))
      (node (ref "L1") (pin "2") (pinfunction "2_2") (pintype "passive"))
      (node (ref "L2") (pin "1") (pinfunction "1_1") (pintype "passive"))
    )
    (net (code "76") (name "Net-(IC15-VPP{slash}~{MCLR}{slash}RE3)") (class "Default")
      (node (ref "IC15") (pin "20") (pinfunction "VPP/~{MCLR}/RE3_20") (pintype "bidirectional"))
      (node (ref "R60") (pin "2") (pinfunction "2_2") (pintype "passive"))
    )
    (net (code "77") (name "Net-(IC17A-C1+)") (class "Default")
      (node (ref "C63") (pin "1") (pinfunction "1_1") (pintype "passive"))
      (node (ref "IC17") (pin "1") (pinfunction "C1+_1") (pintype "bidirectional"))
    )
    (net (code "78") (name "Net-(IC17A-C1-)") (class "Default")
      (node (ref "C63") (pin "2") (pinfunction "2_2") (pintype "passive"))
      (node (ref "IC17") (pin "3") (pinfunction "C1-_3") (pintype "bidirectional"))
    )
    (net (code "79") (name "Net-(IC17A-C2+)") (class "Default")
      (node (ref "C64") (pin "1") (pinfunction "1_1") (pintype "passive"))
      (node (ref "IC17") (pin "4") (pinfunction "C2+_4") (pintype "bidirectional"))
    )
    (net (code "80") (name "Net-(IC17A-C2-)") (class "Default")
      (node (ref "C64") (pin "2") (pinfunction "2_2") (pintype "passive"))
      (node (ref "IC17") (pin "5") (pinfunction "C2-_5") (pintype "bidirectional"))
    )
    (net (code "81") (name "Net-(IC17A-R2OUT)") (class "Default")
      (node (ref "IC17") (pin "9") (pinfunction "R2OUT_9") (pintype "output"))
      (node (ref "X15") (pin "1") (pinfunction "S_1") (pintype "passive"))
    )
    (net (code "82") (name "Net-(IC17A-T2IN)") (class "Default")
      (node (ref "IC17") (pin "10") (pinfunction "T2IN_10") (pintype "input"))
      (node (ref "X16") (pin "1") (pinfunction "S_1") (pintype "passive"))
    )
    (net (code "83") (name "Net-(IC17A-V+)") (class "Default")
      (node (ref "C62") (pin "1") (pinfunction "1_1") (pintype "passive"))
      (node (ref "IC17") (pin "2") (pinfunction "V+_2") (pintype "bidirectional"))
    )
    (net (code "84") (name "Net-(IC17A-V-)") (class "Default")
      (node (ref "C61") (pin "1") (pinfunction "1_1") (pintype "passive"))
      (node (ref "IC17") (pin "6") (pinfunction "V-_6") (pintype "bidirectional"))
    )
    (net (code "85") (name "Net-(INPA-S)") (class "Default")
      (node (ref "INP") (pin "1") (pinfunction "S_1") (pintype "passive"))
      (node (ref "U$1") (pin "IN2") (pinfunction "IN2_IN2") (pintype "bidirectional"))
    )
    (net (code "86") (name "Net-(INPB-S)") (class "Default")
      (node (ref "INP") (pin "10") (pinfunction "S_10") (pintype "passive"))
      (node (ref "U$1") (pin "IN1") (pinfunction "IN1_IN1") (pintype "bidirectional"))
    )
    (net (code "87") (name "Net-(INPC-S)") (class "Default")
      (node (ref "INP") (pin "2") (pinfunction "S_2") (pintype "passive"))
      (node (ref "U$1") (pin "IN3") (pinfunction "IN3_IN3") (pintype "bidirectional"))
    )
    (net (code "88") (name "Net-(INPD-S)") (class "Default")
      (node (ref "INP") (pin "3") (pinfunction "S_3") (pintype "passive"))
      (node (ref "U$1") (pin "IN4") (pinfunction "IN4_IN4") (pintype "bidirectional"))
    )
    (net (code "89") (name "Net-(INPF-S)") (class "Default")
      (node (ref "INP") (pin "5") (pinfunction "S_5") (pintype "passive"))
      (node (ref "U$1") (pin "IN6") (pinfunction "IN6_IN6") (pintype "bidirectional"))
    )
    (net (code "90") (name "Net-(INPG-S)") (class "Default")
      (node (ref "INP") (pin "6") (pinfunction "S_6") (pintype "passive"))
      (node (ref "U$1") (pin "IN7") (pinfunction "IN7_IN7") (pintype "bidirectional"))
    )
    (net (code "91") (name "Net-(INPH-S)") (class "Default")
      (node (ref "INP") (pin "7") (pinfunction "S_7") (pintype "passive"))
      (node (ref "U$1") (pin "IN8") (pinfunction "IN8_IN8") (pintype "bidirectional"))
    )
    (net (code "92") (name "Net-(LED1-PadA)") (class "Default")
      (node (ref "LED1") (pin "A") (pinfunction "A_A") (pintype "passive"))
      (node (ref "R31") (pin "1") (pinfunction "1_1") (pintype "passive"))
    )
    (net (code "93") (name "Net-(LED2-PadA)") (class "Default")
      (node (ref "LED2") (pin "A") (pinfunction "A_A") (pintype "passive"))
      (node (ref "R32") (pin "1") (pinfunction "1_1") (pintype "passive"))
    )
    (net (code "94") (name "Net-(LED3-PadA)") (class "Default")
      (node (ref "LED3") (pin "A") (pinfunction "A_A") (pintype "passive"))
      (node (ref "R33") (pin "1") (pinfunction "1_1") (pintype "passive"))
    )
    (net (code "95") (name "Net-(LED4-PadA)") (class "Default")
      (node (ref "LED4") (pin "A") (pinfunction "A_A") (pintype "passive"))
      (node (ref "R34") (pin "1") (pinfunction "1_1") (pintype "passive"))
    )
    (net (code "96") (name "Net-(LED5-PadA)") (class "Default")
      (node (ref "LED5") (pin "A") (pinfunction "A_A") (pintype "passive"))
      (node (ref "R35") (pin "1") (pinfunction "1_1") (pintype "passive"))
    )
    (net (code "97") (name "Net-(LED8-PadA)") (class "Default")
      (node (ref "LED8") (pin "A") (pinfunction "A_A") (pintype "passive"))
      (node (ref "R70") (pin "1") (pinfunction "1_1") (pintype "passive"))
    )
    (net (code "98") (name "Net-(R1-A)") (class "Default")
      (node (ref "R1") (pin "1") (pinfunction "A_1") (pintype "passive"))
      (node (ref "R21") (pin "1") (pinfunction "1_1") (pintype "passive"))
    )
    (net (code "99") (name "Net-(R1-E)") (class "Default")
      (node (ref "R1") (pin "3") (pinfunction "E_3") (pintype "passive"))
      (node (ref "R13") (pin "2") (pinfunction "2_2") (pintype "passive"))
    )
    (net (code "100") (name "Net-(R2-A)") (class "Default")
      (node (ref "R2") (pin "1") (pinfunction "A_1") (pintype "passive"))
      (node (ref "R22") (pin "1") (pinfunction "1_1") (pintype "passive"))
    )
    (net (code "101") (name "Net-(R2-E)") (class "Default")
      (node (ref "R14") (pin "2") (pinfunction "2_2") (pintype "passive"))
      (node (ref "R2") (pin "3") (pinfunction "E_3") (pintype "passive"))
    )
    (net (code "102") (name "Net-(R3-A)") (class "Default")
      (node (ref "R23") (pin "1") (pinfunction "1_1") (pintype "passive"))
      (node (ref "R3") (pin "1") (pinfunction "A_1") (pintype "passive"))
    )
    (net (code "103") (name "Net-(R3-E)") (class "Default")
      (node (ref "R15") (pin "2") (pinfunction "2_2") (pintype "passive"))
      (node (ref "R3") (pin "3") (pinfunction "E_3") (pintype "passive"))
    )
    (net (code "104") (name "Net-(R4-A)") (class "Default")
      (node (ref "R24") (pin "1") (pinfunction "1_1") (pintype "passive"))
      (node (ref "R4") (pin "1") (pinfunction "A_1") (pintype "passive"))
    )
    (net (code "105") (name "Net-(R4-E)") (class "Default")
      (node (ref "R16") (pin "2") (pinfunction "2_2") (pintype "passive"))
      (node (ref "R4") (pin "3") (pinfunction "E_3") (pintype "passive"))
    )
    (net (code "106") (name "Net-(R5-A)") (class "Default")
      (node (ref "R25") (pin "1") (pinfunction "1_1") (pintype "passive"))
      (node (ref "R5") (pin "1") (pinfunction "A_1") (pintype "passive"))
    )
    (net (code "107") (name "Net-(R5-E)") (class "Default")
      (node (ref "R12") (pin "2") (pinfunction "2_2") (pintype "passive"))
      (node (ref "R5") (pin "3") (pinfunction "E_3") (pintype "passive"))
    )
    (net (code "108") (name "Net-(R6-A)") (class "Default")
      (node (ref "R26") (pin "1") (pinfunction "1_1") (pintype "passive"))
      (node (ref "R6") (pin "1") (pinfunction "A_1") (pintype "passive"))
    )
    (net (code "109") (name "Net-(R6-E)") (class "Default")
      (node (ref "R17") (pin "2") (pinfunction "2_2") (pintype "passive"))
      (node (ref "R6") (pin "3") (pinfunction "E_3") (pintype "passive"))
    )
    (net (code "110") (name "Net-(R7-A)") (class "Default")
      (node (ref "R27") (pin "1") (pinfunction "1_1") (pintype "passive"))
      (node (ref "R7") (pin "1") (pinfunction "A_1") (pintype "passive"))
    )
    (net (code "111") (name "Net-(R7-E)") (class "Default")
      (node (ref "R18") (pin "1") (pinfunction "1_1") (pintype "passive"))
      (node (ref "R7") (pin "3") (pinfunction "E_3") (pintype "passive"))
    )
    (net (code "112") (name "Net-(R8-A)") (class "Default")
      (node (ref "R28") (pin "1") (pinfunction "1_1") (pintype "passive"))
      (node (ref "R8") (pin "1") (pinfunction "A_1") (pintype "passive"))
    )
    (net (code "113") (name "Net-(R8-E)") (class "Default")
      (node (ref "R19") (pin "1") (pinfunction "1_1") (pintype "passive"))
      (node (ref "R8") (pin "3") (pinfunction "E_3") (pintype "passive"))
    )
    (net (code "114") (name "Net-(R9-A)") (class "Default")
      (node (ref "R29") (pin "1") (pinfunction "1_1") (pintype "passive"))
      (node (ref "R9") (pin "1") (pinfunction "A_1") (pintype "passive"))
    )
    (net (code "115") (name "Net-(R9-E)") (class "Default")
      (node (ref "R11") (pin "2") (pinfunction "2_2") (pintype "passive"))
      (node (ref "R9") (pin "3") (pinfunction "E_3") (pintype "passive"))
    )
    (net (code "116") (name "Net-(R10-A)") (class "Default")
      (node (ref "R10") (pin "1") (pinfunction "A_1") (pintype "passive"))
      (node (ref "R30") (pin "1") (pinfunction "1_1") (pintype "passive"))
    )
    (net (code "117") (name "Net-(R10-E)") (class "Default")
      (node (ref "R10") (pin "3") (pinfunction "E_3") (pintype "passive"))
      (node (ref "R20") (pin "1") (pinfunction "1_1") (pintype "passive"))
    )
    (net (code "118") (name "Net-(R60-Pad1)") (class "Default")
      (node (ref "R60") (pin "1") (pinfunction "1_1") (pintype "passive"))
      (node (ref "R71") (pin "2") (pinfunction "2_2") (pintype "passive"))
      (node (ref "SV7") (pin "1") (pinfunction "1_1") (pintype "passive"))
    )
    (net (code "119") (name "Net-(S6-+)") (class "Default")
      (node (ref "R62") (pin "1") (pinfunction "1_1") (pintype "passive"))
      (node (ref "S6") (pin "5") (pinfunction "+_5") (pintype "bidirectional"))
    )
    (net (code "120") (name "Net-(X17B-S)") (class "Default")
      (node (ref "C51") (pin "1") (pinfunction "1_1") (pintype "passive"))
      (node (ref "R61") (pin "1") (pinfunction "1_1") (pintype "passive"))
      (node (ref "R71") (pin "1") (pinfunction "1_1") (pintype "passive"))
      (node (ref "S6") (pin "4") (pinfunction "4_4") (pintype "bidirectional"))
      (node (ref "X17") (pin "2") (pinfunction "S_2") (pintype "passive"))
    )
    (net (code "121") (name "VCC") (class "Default")
      (node (ref "C65") (pin "1") (pinfunction "1_1") (pintype "passive"))
      (node (ref "C68") (pin "1") (pinfunction "1_1") (pintype "passive"))
      (node (ref "C69") (pin "1") (pinfunction "1_1") (pintype "passive"))
      (node (ref "JMP6") (pin "2") (pinfunction "2_2") (pintype "passive"))
      (node (ref "Q3") (pin "1") (pinfunction "OE_1") (pintype "input"))
      (node (ref "Q3") (pin "4") (pinfunction "VCC_4") (pintype "power_in"))
      (node (ref "R66") (pin "1") (pinfunction "1_1") (pintype "passive"))
    )
    (net (code "122") (name "VDD") (class "Default")
      (node (ref "C1") (pin "1") (pinfunction "1_1") (pintype "passive"))
      (node (ref "C10") (pin "1") (pinfunction "1_1") (pintype "passive"))
      (node (ref "C4") (pin "2") (pinfunction "2_2") (pintype "passive"))
      (node (ref "C5") (pin "1") (pinfunction "1_1") (pintype "passive"))
      (node (ref "C58") (pin "1") (pinfunction "1_1") (pintype "passive"))
      (node (ref "C59") (pin "1") (pinfunction "1_1") (pintype "passive"))
      (node (ref "D1") (pin "C") (pinfunction "C_C") (pintype "passive"))
      (node (ref "IC16") (pin "3") (pinfunction "3_3") (pintype "bidirectional"))
      (node (ref "IC16") (pin "4") (pinfunction "4_4") (pintype "bidirectional"))
      (node (ref "IC2") (pin "2") (pinfunction "2_2") (pintype "passive"))
      (node (ref "IC4") (pin "3") (pinfunction "VO_3") (pintype "passive"))
      (node (ref "INP") (pin "8") (pinfunction "S_8") (pintype "passive"))
      (node (ref "J1") (pin "12") (pinfunction "12_12") (pintype "passive"))
      (node (ref "J2") (pin "2") (pinfunction "2_2") (pintype "passive"))
      (node (ref "JMP6") (pin "1") (pinfunction "1_1") (pintype "passive"))
      (node (ref "L1") (pin "1") (pinfunction "1_1") (pintype "passive"))
      (node (ref "L2") (pin "2") (pinfunction "2_2") (pintype "passive"))
      (node (ref "R33") (pin "2") (pinfunction "2_2") (pintype "passive"))
      (node (ref "R61") (pin "2") (pinfunction "2_2") (pintype "passive"))
      (node (ref "R66") (pin "2") (pinfunction "2_2") (pintype "passive"))
      (node (ref "REFVDD") (pin "TP") (pinfunction "TP_TP") (pintype "input"))
      (node (ref "SL4") (pin "2") (pinfunction "2_2") (pintype "passive"))
      (node (ref "SPI_IN") (pin "7") (pinfunction "S_7") (pintype "passive"))
      (node (ref "SPI_OUT") (pin "7") (pinfunction "S_7") (pintype "passive"))
      (node (ref "SV7") (pin "2") (pinfunction "2_2") (pintype "passive"))
      (node (ref "U$1") (pin "VCC") (pinfunction "VCC_VCC") (pintype "bidirectional"))
    )
    (net (code "123") (name "VSS") (class "Default")
      (node (ref "C1") (pin "2") (pinfunction "2_2") (pintype "passive"))
      (node (ref "C10") (pin "2") (pinfunction "2_2") (pintype "passive"))
      (node (ref "C11") (pin "2") (pinfunction "2_2") (pintype "passive"))
      (node (ref "C12") (pin "2") (pinfunction "2_2") (pintype "passive"))
      (node (ref "C4") (pin "1") (pinfunction "1_1") (pintype "passive"))
      (node (ref "C5") (pin "2") (pinfunction "2_2") (pintype "passive"))
      (node (ref "C51") (pin "2") (pinfunction "2_2") (pintype "passive"))
      (node (ref "C52") (pin "2") (pinfunction "2_2") (pintype "passive"))
      (node (ref "C53") (pin "2") (pinfunction "2_2") (pintype "passive"))
      (node (ref "C54") (pin "2") (pinfunction "2_2") (pintype "passive"))
      (node (ref "C57") (pin "2") (pinfunction "2_2") (pintype "passive"))
      (node (ref "C58") (pin "2") (pinfunction "2_2") (pintype "passive"))
      (node (ref "C59") (pin "2") (pinfunction "2_2") (pintype "passive"))
      (node (ref "C6") (pin "2") (pinfunction "2_2") (pintype "passive"))
      (node (ref "C60") (pin "2") (pinfunction "2_2") (pintype "passive"))
      (node (ref "C61") (pin "2") (pinfunction "2_2") (pintype "passive"))
      (node (ref "C62") (pin "2") (pinfunction "2_2") (pintype "passive"))
      (node (ref "C67") (pin "2") (pinfunction "2_2") (pintype "passive"))
      (node (ref "C7") (pin "2") (pinfunction "2_2") (pintype "passive"))
      (node (ref "C8") (pin "2") (pinfunction "2_2") (pintype "passive"))
      (node (ref "C9") (pin "2") (pinfunction "2_2") (pintype "passive"))
      (node (ref "D1") (pin "A") (pinfunction "A_A") (pintype "passive"))
      (node (ref "IC1") (pin "9") (pinfunction "GND_9") (pintype "power_in"))
      (node (ref "IC15") (pin "31") (pinfunction "VSS_2_31") (pintype "bidirectional"))
      (node (ref "IC15") (pin "6") (pinfunction "VSS_1_6") (pintype "bidirectional"))
      (node (ref "IC16") (pin "1") (pinfunction "1_1") (pintype "bidirectional"))
      (node (ref "IC16") (pin "2") (pinfunction "2_2") (pintype "bidirectional"))
      (node (ref "IC2") (pin "1") (pinfunction "1_1") (pintype "passive"))
      (node (ref "IC3") (pin "4") (pinfunction "GND_4") (pintype "power_in"))
      (node (ref "IC4") (pin "2") (pinfunction "GND_2") (pintype "passive"))
      (node (ref "IC5") (pin "2") (pinfunction "GND_2") (pintype "passive"))
      (node (ref "IC6") (pin "2") (pinfunction "GND_2") (pintype "passive"))
      (node (ref "INP") (pin "9") (pinfunction "S_9") (pintype "passive"))
      (node (ref "J1") (pin "11") (pinfunction "11_11") (pintype "passive"))
      (node (ref "J2") (pin "1") (pinfunction "1_1") (pintype "passive"))
      (node (ref "JMP5") (pin "1") (pinfunction "1_1") (pintype "passive"))
      (node (ref "LED1") (pin "C") (pinfunction "C_C") (pintype "passive"))
      (node (ref "LED2") (pin "C") (pinfunction "C_C") (pintype "passive"))
      (node (ref "LED3") (pin "C") (pinfunction "C_C") (pintype "passive"))
      (node (ref "LED4") (pin "C") (pinfunction "C_C") (pintype "passive"))
      (node (ref "LED5") (pin "C") (pinfunction "C_C") (pintype "passive"))
      (node (ref "LED8") (pin "C") (pinfunction "C_C") (pintype "passive"))
      (node (ref "OUTP") (pin "9") (pinfunction "S_9") (pintype "passive"))
      (node (ref "R21") (pin "2") (pinfunction "2_2") (pintype "passive"))
      (node (ref "R22") (pin "2") (pinfunction "2_2") (pintype "passive"))
      (node (ref "R23") (pin "2") (pinfunction "2_2") (pintype "passive"))
      (node (ref "R24") (pin "2") (pinfunction "2_2") (pintype "passive"))
      (node (ref "R25") (pin "2") (pinfunction "2_2") (pintype "passive"))
      (node (ref "R26") (pin "2") (pinfunction "2_2") (pintype "passive"))
      (node (ref "R27") (pin "2") (pinfunction "2_2") (pintype "passive"))
      (node (ref "R28") (pin "2") (pinfunction "2_2") (pintype "passive"))
      (node (ref "R29") (pin "2") (pinfunction "2_2") (pintype "passive"))
      (node (ref "R30") (pin "2") (pinfunction "2_2") (pintype "passive"))
      (node (ref "R67") (pin "2") (pinfunction "2_2") (pintype "passive"))
      (node (ref "REFVSS") (pin "TP") (pinfunction "TP_TP") (pintype "input"))
      (node (ref "RS-232-3") (pin "1") (pinfunction "1_1") (pintype "passive"))
      (node (ref "RS232-3") (pin "1") (pinfunction "1_1") (pintype "passive"))
      (node (ref "S6") (pin "2") (pinfunction "2_2") (pintype "bidirectional"))
      (node (ref "S6") (pin "6") (pinfunction "-_6") (pintype "bidirectional"))
      (node (ref "SL1") (pin "1") (pinfunction "1_1") (pintype "passive"))
      (node (ref "SL2") (pin "1") (pinfunction "1_1") (pintype "passive"))
      (node (ref "SL3") (pin "1") (pinfunction "1_1") (pintype "passive"))
      (node (ref "SL4") (pin "1") (pinfunction "1_1") (pintype "passive"))
      (node (ref "SPI_IN") (pin "8") (pinfunction "S_8") (pintype "passive"))
      (node (ref "SPI_OUT") (pin "8") (pinfunction "S_8") (pintype "passive"))
      (node (ref "SV7") (pin "3") (pinfunction "3_3") (pintype "passive"))
      (node (ref "SV8") (pin "1") (pinfunction "1_1") (pintype "passive"))
      (node (ref "U$1") (pin "GND") (pinfunction "GND_GND") (pintype "bidirectional"))
      (node (ref "X17") (pin "1") (pinfunction "S_1") (pintype "passive"))
    )
    (net (code "124") (name "unconnected-(IC2-Pad3)") (class "Default")
      (node (ref "IC2") (pin "3") (pinfunction "3_3") (pintype "passive"))
    )
    (net (code "125") (name "unconnected-(IC3-OPT-Pad3)") (class "Default")
      (node (ref "IC3") (pin "3") (pinfunction "OPT_3") (pintype "output"))
    )
    (net (code "126") (name "unconnected-(IC3-TRM-Pad5)") (class "Default")
      (node (ref "IC3") (pin "5") (pinfunction "TRM_5") (pintype "input"))
    )
    (net (code "127") (name "unconnected-(IC15-RF6-Pad14)") (class "Default")
      (node (ref "IC15") (pin "14") (pinfunction "RF6_14") (pintype "bidirectional"))
    )
    (net (code "128") (name "unconnected-(IC15-RF7-Pad15)") (class "Default")
      (node (ref "IC15") (pin "15") (pinfunction "RF7_15") (pintype "bidirectional"))
    )
    (net (code "129") (name "unconnected-(JMP5-Pad3)") (class "Default")
      (node (ref "JMP5") (pin "3") (pinfunction "3_3") (pintype "passive"))
    )
    (net (code "130") (name "unconnected-(JMP6-Pad3)") (class "Default")
      (node (ref "JMP6") (pin "3") (pinfunction "3_3") (pintype "passive"))
    )
    (net (code "131") (name "unconnected-(RS-232-3-Pad4)") (class "Default")
      (node (ref "RS-232-3") (pin "4") (pinfunction "4_4") (pintype "passive"))
    )
    (net (code "132") (name "unconnected-(RS232-3-Pad4)") (class "Default")
      (node (ref "RS232-3") (pin "4") (pinfunction "4_4") (pintype "passive"))
    )
    (net (code "133") (name "unconnected-(S6-Pad1)") (class "Default")
      (node (ref "S6") (pin "1") (pinfunction "1_1") (pintype "bidirectional"))
    )
    (net (code "134") (name "unconnected-(S6-Pad3)") (class "Default")
      (node (ref "S6") (pin "3") (pinfunction "3_3") (pintype "bidirectional"))
    )
    (net (code "135") (name "unconnected-(SV7-Pad6)") (class "Default")
      (node (ref "SV7") (pin "6") (pinfunction "6_6") (pintype "passive"))
    )
  )
)
